# 01power.net
KiCad netlist of a schematic drawn in Altium Designer
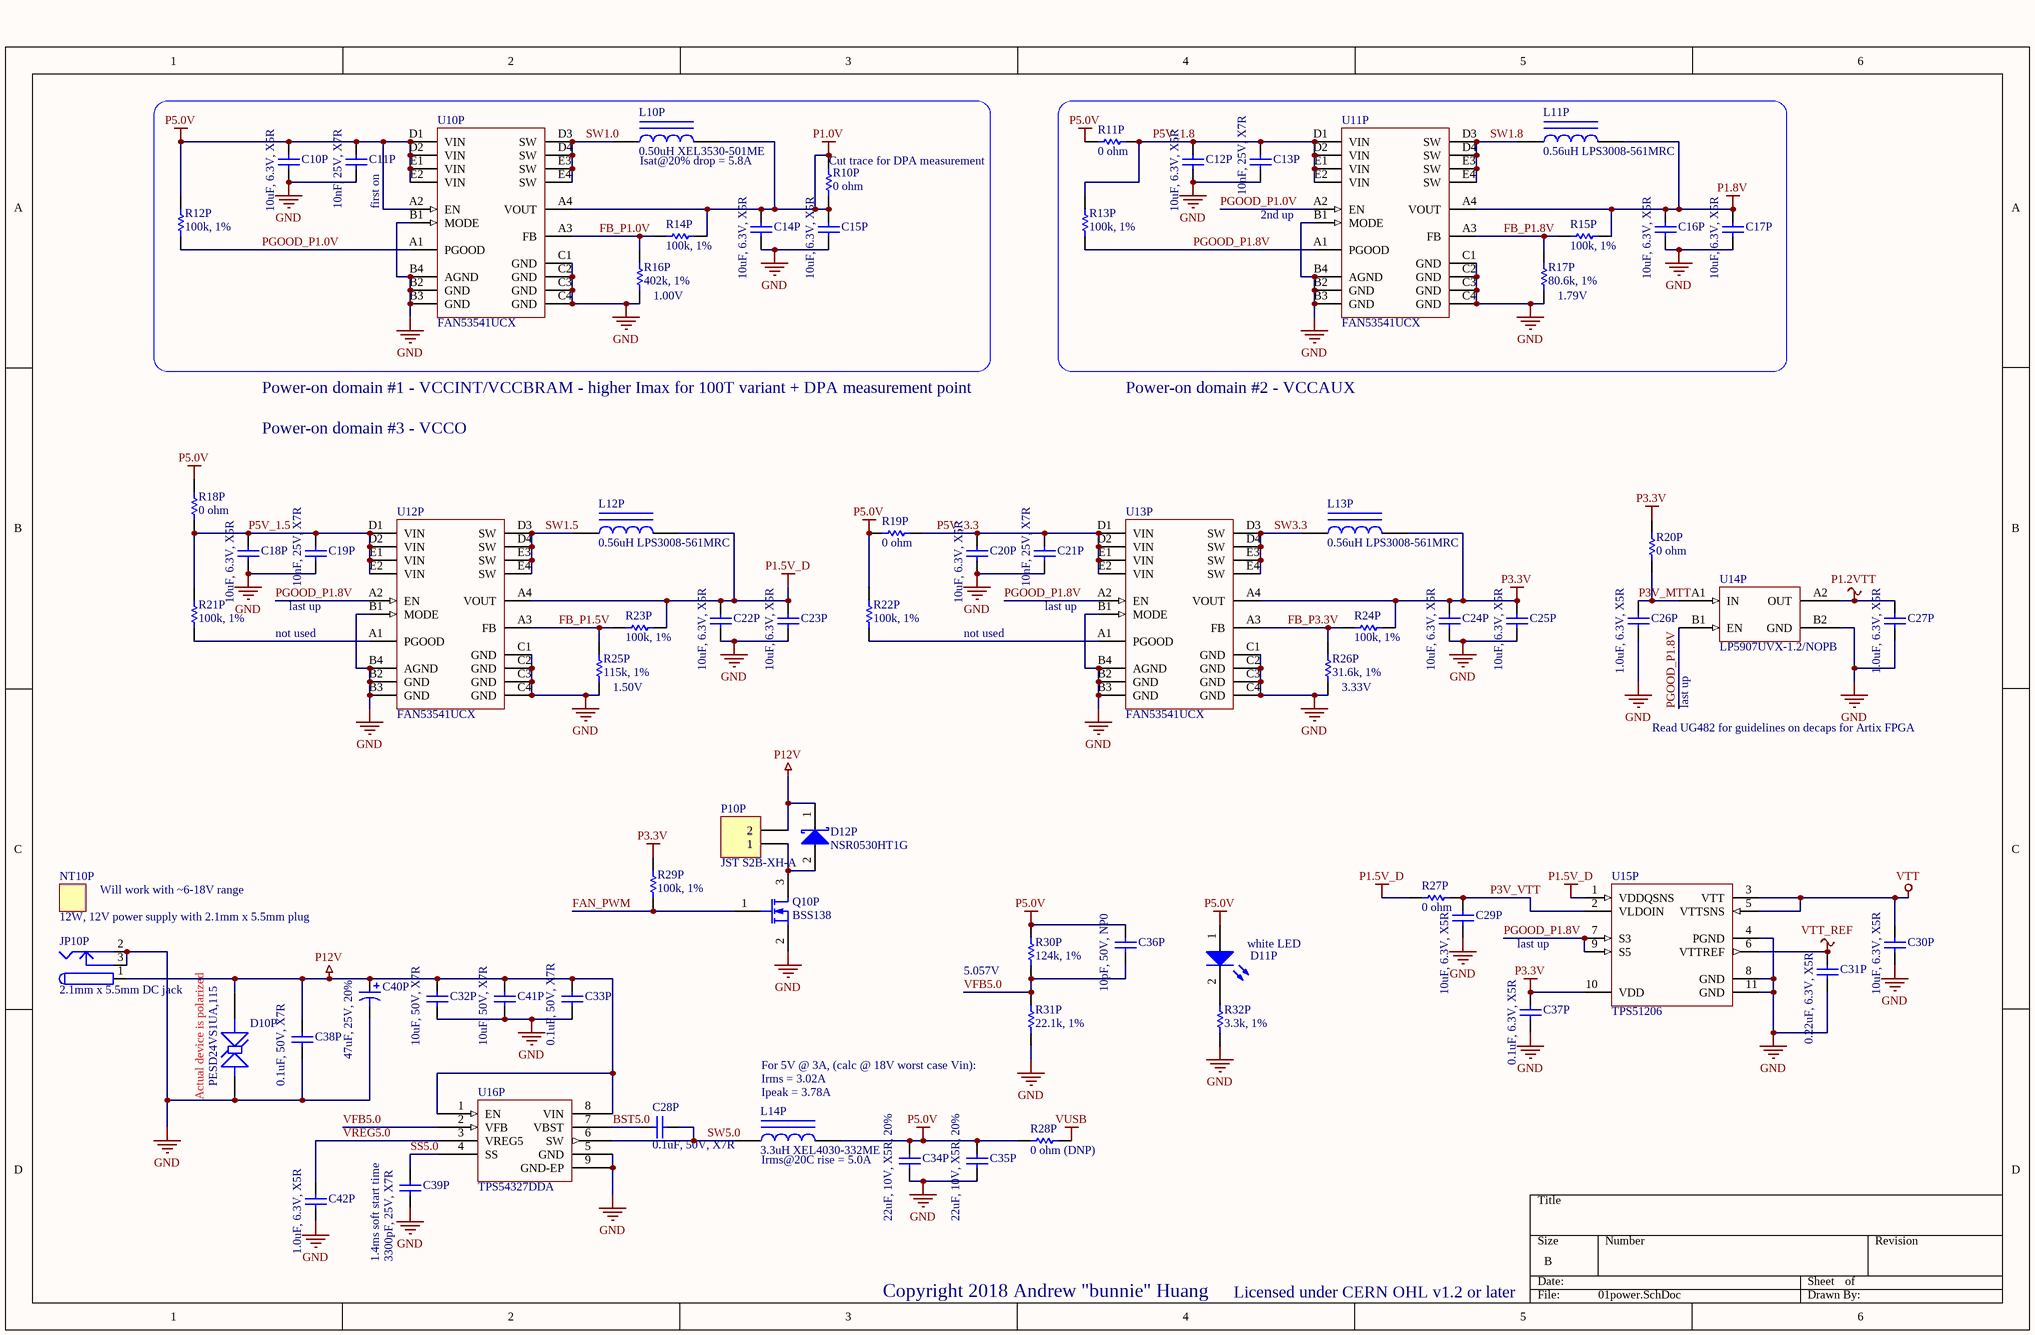
[diagram p0: 01power.SchDoc]

(export (version "E")
  (design (tool "Eeschema 10.0.6"))
  (components
    (comp (ref "C10P")
      (value "10uF, 6.3V, X5R")
      (footprint "CAPC1608N")
      (description "Capacitor (Semiconductor SIM Model)")
      (fields (field (name "MPN") "CL10A106MQ8NNNC"))
      (libsource (lib "Miscellaneous Devices") (part "Cap Semi"))
    )
    (comp (ref "C11P")
      (value "10nF, 25V, X7R")
      (footprint "CAPC1005N")
      (description "Capacitor (Semiconductor SIM Model)")
      (fields (field (name "MPN") "CL05B103KA5NNNC"))
      (libsource (lib "Miscellaneous Devices") (part "Cap Semi"))
    )
    (comp (ref "C12P")
      (value "10uF, 6.3V, X5R")
      (footprint "CAPC1608N")
      (description "Capacitor (Semiconductor SIM Model)")
      (fields (field (name "MPN") "CL10A106MQ8NNNC"))
      (libsource (lib "Miscellaneous Devices") (part "Cap Semi"))
    )
    (comp (ref "C13P")
      (value "10nF, 25V, X7R")
      (footprint "CAPC1005N")
      (description "Capacitor (Semiconductor SIM Model)")
      (fields (field (name "MPN") "CL05B103KA5NNNC"))
      (libsource (lib "Miscellaneous Devices") (part "Cap Semi"))
    )
    (comp (ref "C14P")
      (value "10uF, 6.3V, X5R")
      (footprint "CAPC1608N")
      (description "Capacitor (Semiconductor SIM Model)")
      (fields (field (name "MPN") "CL10A106MQ8NNNC"))
      (libsource (lib "Miscellaneous Devices") (part "Cap Semi"))
    )
    (comp (ref "C15P")
      (value "10uF, 6.3V, X5R")
      (footprint "CAPC1608N")
      (description "Capacitor (Semiconductor SIM Model)")
      (fields (field (name "MPN") "CL10A106MQ8NNNC"))
      (libsource (lib "Miscellaneous Devices") (part "Cap Semi"))
    )
    (comp (ref "C16P")
      (value "10uF, 6.3V, X5R")
      (footprint "CAPC1608N")
      (description "Capacitor (Semiconductor SIM Model)")
      (fields (field (name "MPN") "CL10A106MQ8NNNC"))
      (libsource (lib "Miscellaneous Devices") (part "Cap Semi"))
    )
    (comp (ref "C17P")
      (value "10uF, 6.3V, X5R")
      (footprint "CAPC1608N")
      (description "Capacitor (Semiconductor SIM Model)")
      (fields (field (name "MPN") "CL10A106MQ8NNNC"))
      (libsource (lib "Miscellaneous Devices") (part "Cap Semi"))
    )
    (comp (ref "C18P")
      (value "10uF, 6.3V, X5R")
      (footprint "CAPC1608N")
      (description "Capacitor (Semiconductor SIM Model)")
      (fields (field (name "MPN") "CL10A106MQ8NNNC"))
      (libsource (lib "Miscellaneous Devices") (part "Cap Semi"))
    )
    (comp (ref "C19P")
      (value "10nF, 25V, X7R")
      (footprint "CAPC1005N")
      (description "Capacitor (Semiconductor SIM Model)")
      (fields (field (name "MPN") "CL05B103KA5NNNC"))
      (libsource (lib "Miscellaneous Devices") (part "Cap Semi"))
    )
    (comp (ref "C20P")
      (value "10uF, 6.3V, X5R")
      (footprint "CAPC1608N")
      (description "Capacitor (Semiconductor SIM Model)")
      (fields (field (name "MPN") "CL10A106MQ8NNNC"))
      (libsource (lib "Miscellaneous Devices") (part "Cap Semi"))
    )
    (comp (ref "C21P")
      (value "10nF, 25V, X7R")
      (footprint "CAPC1005N")
      (description "Capacitor (Semiconductor SIM Model)")
      (fields (field (name "MPN") "CL05B103KA5NNNC"))
      (libsource (lib "Miscellaneous Devices") (part "Cap Semi"))
    )
    (comp (ref "C22P")
      (value "10uF, 6.3V, X5R")
      (footprint "CAPC1608N")
      (description "Capacitor (Semiconductor SIM Model)")
      (fields (field (name "MPN") "CL10A106MQ8NNNC"))
      (libsource (lib "Miscellaneous Devices") (part "Cap Semi"))
    )
    (comp (ref "C23P")
      (value "10uF, 6.3V, X5R")
      (footprint "CAPC1608N")
      (description "Capacitor (Semiconductor SIM Model)")
      (fields (field (name "MPN") "CL10A106MQ8NNNC"))
      (libsource (lib "Miscellaneous Devices") (part "Cap Semi"))
    )
    (comp (ref "C24P")
      (value "10uF, 6.3V, X5R")
      (footprint "CAPC1608N")
      (description "Capacitor (Semiconductor SIM Model)")
      (fields (field (name "MPN") "CL10A106MQ8NNNC"))
      (libsource (lib "Miscellaneous Devices") (part "Cap Semi"))
    )
    (comp (ref "C25P")
      (value "10uF, 6.3V, X5R")
      (footprint "CAPC1608N")
      (description "Capacitor (Semiconductor SIM Model)")
      (fields (field (name "MPN") "CL10A106MQ8NNNC"))
      (libsource (lib "Miscellaneous Devices") (part "Cap Semi"))
    )
    (comp (ref "C26P")
      (value "1.0uF, 6.3V, X5R")
      (footprint "CAPC0603X03L")
      (description "Capacitor (Semiconductor SIM Model)")
      (fields (field (name "MPN") "CL03A105KQ3CSNC"))
      (libsource (lib "Miscellaneous Devices") (part "Cap Semi"))
    )
    (comp (ref "C27P")
      (value "1.0uF, 6.3V, X5R")
      (footprint "CAPC0603X03L")
      (description "Capacitor (Semiconductor SIM Model)")
      (fields (field (name "MPN") "CL03A105KQ3CSNC"))
      (libsource (lib "Miscellaneous Devices") (part "Cap Semi"))
    )
    (comp (ref "C28P")
      (value "0.1uF, 50V, X7R")
      (footprint "CAPC2012N")
      (description "Capacitor (Semiconductor SIM Model)")
      (fields (field (name "MPN") "CL21B104KBCNNWC"))
      (libsource (lib "Miscellaneous Devices") (part "Cap Semi"))
    )
    (comp (ref "C29P")
      (value "10uF, 6.3V, X5R")
      (footprint "CAPC1608N")
      (description "Capacitor (Semiconductor SIM Model)")
      (fields (field (name "MPN") "CL10A106MQ8NNNC"))
      (libsource (lib "Miscellaneous Devices") (part "Cap Semi"))
    )
    (comp (ref "C30P")
      (value "10uF, 6.3V, X5R")
      (footprint "CAPC1608N")
      (description "Capacitor (Semiconductor SIM Model)")
      (fields (field (name "MPN") "CL10A106MQ8NNNC"))
      (libsource (lib "Miscellaneous Devices") (part "Cap Semi"))
    )
    (comp (ref "C31P")
      (value "0.22uF, 6.3V, X5R")
      (footprint "CAPC0603X03L")
      (description "Capacitor (Semiconductor SIM Model)")
      (fields (field (name "MPN") "CL03A224MQ3NNNC"))
      (libsource (lib "Miscellaneous Devices") (part "Cap Semi"))
    )
    (comp (ref "C32P")
      (value "10uF, 50V, X7R")
      (footprint "CAPC3216N")
      (description "Capacitor (Semiconductor SIM Model)")
      (fields (field (name "MPN") "CL31A106KBHNNNE"))
      (libsource (lib "Miscellaneous Devices") (part "Cap Semi"))
    )
    (comp (ref "C33P")
      (value "0.1uF, 50V, X7R")
      (footprint "CAPC2012N")
      (description "Capacitor (Semiconductor SIM Model)")
      (fields (field (name "MPN") "CL21B104KBCNNWC"))
      (libsource (lib "Miscellaneous Devices") (part "Cap Semi"))
    )
    (comp (ref "C34P")
      (value "22uF, 10V, X5R, 20%")
      (footprint "CAPC2012N")
      (description "Capacitor (Semiconductor SIM Model)")
      (fields
        (field (name "MFG") "Murata")
        (field (name "MPN") "GRM21BR61A226ME51L")
        (field (name "PUBLISHER") "Altium Limited")
      )
      (libsource (lib "Miscellaneous Devices") (part "Cap Semi"))
    )
    (comp (ref "C35P")
      (value "22uF, 10V, X5R, 20%")
      (footprint "CAPC2012N")
      (description "Capacitor (Semiconductor SIM Model)")
      (fields
        (field (name "MFG") "Murata")
        (field (name "MPN") "GRM21BR61A226ME51L")
        (field (name "PUBLISHER") "Altium Limited")
      )
      (libsource (lib "Miscellaneous Devices") (part "Cap Semi"))
    )
    (comp (ref "C36P")
      (value "10pF, 50V, NP0")
      (footprint "CAPC1005N")
      (description "Capacitor (Semiconductor SIM Model)")
      (fields (field (name "MPN") "GCM1555C1H100JA16D"))
      (libsource (lib "Miscellaneous Devices") (part "Cap Semi"))
    )
    (comp (ref "C37P")
      (value "0.1uF, 6.3V, X5R")
      (footprint "CAPC0603X03L")
      (description "Capacitor (Semiconductor SIM Model)")
      (fields (field (name "MPN") "CL03A104KQ3NNNC"))
      (libsource (lib "Miscellaneous Devices") (part "Cap Semi"))
    )
    (comp (ref "C38P")
      (value "0.1uF, 50V, X7R")
      (footprint "CAPC2012N")
      (description "Capacitor (Semiconductor SIM Model)")
      (fields (field (name "MPN") "CL21B104KBCNNWC"))
      (libsource (lib "Miscellaneous Devices") (part "Cap Semi"))
    )
    (comp (ref "C39P")
      (value "3300pF, 25V, X7R")
      (footprint "CAPC1005N")
      (description "Capacitor (Semiconductor SIM Model)")
      (fields (field (name "MPN") "CL05B332KA5NNNC"))
      (libsource (lib "Miscellaneous Devices") (part "Cap Semi"))
    )
    (comp (ref "C40P")
      (value "47uF, 25V, 20%")
      (footprint "CAPAE7066X61N")
      (description "Polarized Capacitor (Radial)")
      (fields (field (name "MPN") "UCL1E470MCL1GS"))
      (libsource (lib "Miscellaneous Devices") (part "Cap Pol1"))
    )
    (comp (ref "C41P")
      (value "10uF, 50V, X7R")
      (footprint "CAPC3216N")
      (description "Capacitor (Semiconductor SIM Model)")
      (fields (field (name "MPN") "CL31A106KBHNNNE"))
      (libsource (lib "Miscellaneous Devices") (part "Cap Semi"))
    )
    (comp (ref "C42P")
      (value "1.0uF, 6.3V, X5R")
      (footprint "CAPC0603X03L")
      (description "Capacitor (Semiconductor SIM Model)")
      (fields (field (name "MPN") "CL03A105KQ3CSNC"))
      (libsource (lib "Miscellaneous Devices") (part "Cap Semi"))
    )
    (comp (ref "D10P")
      (value "PESD24VS1UA,115")
      (footprint "SOD-323")
      (description "Bidirectional zener diode, Vz 17.1V nom")
      (libsource (lib "commonsch") (part "BIDIR_ESD"))
    )
    (comp (ref "D11P")
      (value "white LED")
      (footprint "CD2012-0805")
      (description "Typical RED, GREEN, YELLOW, AMBER GaAs LED")
      (fields (field (name "MPN") "CB-2012QWC-P8"))
      (libsource (lib "Miscellaneous Devices") (part "LED2"))
    )
    (comp (ref "D12P")
      (value "NSR0530HT1G")
      (footprint "SOD-323")
      (description "Schottky Diode")
      (fields (field (name "MPN") "NSR0530H-D"))
      (libsource (lib "Miscellaneous Devices") (part "D Schottky"))
    )
    (comp (ref "JP10P")
      (value "2.1mm x 5.5mm DC jack")
      (footprint "CUI_PJ_002AH_SMT")
      (description "Low Voltage Power Supply Connector")
      (fields (field (name "MPN") "DC-480-2.0A-SMT") (field (name "PUBLISHER") "Altium Limited"))
      (libsource (lib "Miscellaneous Connectors") (part "PWR2.5"))
    )
    (comp (ref "L10P")
      (value "0.50uH XEL3530-501ME")
      (footprint "COILCRAFT_XEL3530")
      (description "Magnetic-Core Inductor")
      (fields (field (name "MPN") "XEL3530-501ME_"))
      (libsource (lib "Miscellaneous Devices") (part "Inductor Iron"))
    )
    (comp (ref "L11P")
      (value "0.56uH LPS3008-561MRC")
      (footprint "COILCRAFT_LPS3008")
      (description "Magnetic-Core Inductor")
      (fields (field (name "MPN") "LPS3008-561MRC"))
      (libsource (lib "Miscellaneous Devices") (part "Inductor Iron"))
    )
    (comp (ref "L12P")
      (value "0.56uH LPS3008-561MRC")
      (footprint "COILCRAFT_LPS3008")
      (description "Magnetic-Core Inductor")
      (fields (field (name "MPN") "LPS3008-561MRC"))
      (libsource (lib "Miscellaneous Devices") (part "Inductor Iron"))
    )
    (comp (ref "L13P")
      (value "0.56uH LPS3008-561MRC")
      (footprint "COILCRAFT_LPS3008")
      (description "Magnetic-Core Inductor")
      (fields (field (name "MPN") "LPS3008-561MRC"))
      (libsource (lib "Miscellaneous Devices") (part "Inductor Iron"))
    )
    (comp (ref "L14P")
      (value "3.3uH XEL4030-332ME")
      (footprint "COILCRAFT_XEL4030")
      (description "Magnetic-Core Inductor")
      (fields (field (name "MPN") "XEL4030-332ME_"))
      (libsource (lib "Miscellaneous Devices") (part "Inductor Iron"))
    )
    (comp (ref "NT10P")
      (value "12W, 12V power supply with 2.1mm x 5.5mm plug")
      (description "Placeholder for non-board BOM items")
      (fields (field (name "MPN") "ANY"))
      (libsource (lib "commonsch") (part "NOTE"))
    )
    (comp (ref "P10P")
      (value "JST S2B-XH-A")
      (footprint "JST_S2B_XH_A")
      (description "Header, 2-Pin")
      (fields (field (name "MPN") "S2B-XH-A"))
      (libsource (lib "Miscellaneous Connectors") (part "Header 2"))
    )
    (comp (ref "Q10P")
      (value "BSS138")
      (footprint "SOT23-3N")
      (description "N-Channel MOSFET")
      (fields (field (name "MPN") "BSS138LT1G") (field (name "PUBLISHER") "Altium Limited"))
      (libsource (lib "Miscellaneous Devices") (part "MOSFET-N"))
    )
    (comp (ref "R10P")
      (value "0 ohm")
      (footprint "RESC1608N")
      (description "Resistor")
      (fields (field (name "MPN") "ANY"))
      (libsource (lib "Miscellaneous Devices") (part "Res1"))
    )
    (comp (ref "R11P")
      (value "0 ohm")
      (footprint "RESC1608N")
      (description "Resistor")
      (fields (field (name "MPN") "ANY"))
      (libsource (lib "Miscellaneous Devices") (part "Res1"))
    )
    (comp (ref "R12P")
      (value "100k, 1%")
      (footprint "RESC1005N")
      (description "Resistor")
      (fields (field (name "MPN") "ANY"))
      (libsource (lib "Miscellaneous Devices") (part "Res1"))
    )
    (comp (ref "R13P")
      (value "100k, 1%")
      (footprint "RESC1005N")
      (description "Resistor")
      (fields (field (name "MPN") "ANY"))
      (libsource (lib "Miscellaneous Devices") (part "Res1"))
    )
    (comp (ref "R14P")
      (value "100k, 1%")
      (footprint "RESC1005N")
      (description "Resistor")
      (fields (field (name "MPN") "ANY"))
      (libsource (lib "Miscellaneous Devices") (part "Res1"))
    )
    (comp (ref "R15P")
      (value "100k, 1%")
      (footprint "RESC1005N")
      (description "Resistor")
      (fields (field (name "MPN") "ANY"))
      (libsource (lib "Miscellaneous Devices") (part "Res1"))
    )
    (comp (ref "R16P")
      (value "402k, 1%")
      (footprint "RESC1005N")
      (description "Resistor")
      (fields (field (name "MPN") "ANY"))
      (libsource (lib "Miscellaneous Devices") (part "Res1"))
    )
    (comp (ref "R17P")
      (value "80.6k, 1%")
      (footprint "RESC1005N")
      (description "Resistor")
      (fields (field (name "MPN") "ANY"))
      (libsource (lib "Miscellaneous Devices") (part "Res1"))
    )
    (comp (ref "R18P")
      (value "0 ohm")
      (footprint "RESC1608N")
      (description "Resistor")
      (fields (field (name "MPN") "ANY"))
      (libsource (lib "Miscellaneous Devices") (part "Res1"))
    )
    (comp (ref "R19P")
      (value "0 ohm")
      (footprint "RESC1608N")
      (description "Resistor")
      (fields (field (name "MPN") "ANY"))
      (libsource (lib "Miscellaneous Devices") (part "Res1"))
    )
    (comp (ref "R20P")
      (value "0 ohm")
      (footprint "RESC1608N")
      (description "Resistor")
      (fields (field (name "MPN") "ANY"))
      (libsource (lib "Miscellaneous Devices") (part "Res1"))
    )
    (comp (ref "R21P")
      (value "100k, 1%")
      (footprint "RESC1005N")
      (description "Resistor")
      (fields (field (name "MPN") "ANY"))
      (libsource (lib "Miscellaneous Devices") (part "Res1"))
    )
    (comp (ref "R22P")
      (value "100k, 1%")
      (footprint "RESC1005N")
      (description "Resistor")
      (fields (field (name "MPN") "ANY"))
      (libsource (lib "Miscellaneous Devices") (part "Res1"))
    )
    (comp (ref "R23P")
      (value "100k, 1%")
      (footprint "RESC1005N")
      (description "Resistor")
      (fields (field (name "MPN") "ANY"))
      (libsource (lib "Miscellaneous Devices") (part "Res1"))
    )
    (comp (ref "R24P")
      (value "100k, 1%")
      (footprint "RESC1005N")
      (description "Resistor")
      (fields (field (name "MPN") "ANY"))
      (libsource (lib "Miscellaneous Devices") (part "Res1"))
    )
    (comp (ref "R25P")
      (value "115k, 1%")
      (footprint "RESC1005N")
      (description "Resistor")
      (fields (field (name "MPN") "ANY"))
      (libsource (lib "Miscellaneous Devices") (part "Res1"))
    )
    (comp (ref "R26P")
      (value "31.6k, 1%")
      (footprint "RESC1005N")
      (description "Resistor")
      (fields (field (name "MPN") "ANY"))
      (libsource (lib "Miscellaneous Devices") (part "Res1"))
    )
    (comp (ref "R27P")
      (value "0 ohm")
      (footprint "RESC1608N")
      (description "Resistor")
      (fields (field (name "MPN") "ANY"))
      (libsource (lib "Miscellaneous Devices") (part "Res1"))
    )
    (comp (ref "R28P")
      (value "0 ohm (DNP)")
      (footprint "RESC1608N")
      (description "Resistor")
      (fields (field (name "MPN") "DNP"))
      (libsource (lib "Miscellaneous Devices") (part "Res1"))
    )
    (comp (ref "R29P")
      (value "100k, 1%")
      (footprint "RESC1005N")
      (description "Resistor")
      (fields (field (name "MPN") "ANY"))
      (libsource (lib "Miscellaneous Devices") (part "Res1"))
    )
    (comp (ref "R30P")
      (value "124k, 1%")
      (footprint "RESC1005N")
      (description "Resistor")
      (fields (field (name "MPN") "ANY"))
      (libsource (lib "Miscellaneous Devices") (part "Res1"))
    )
    (comp (ref "R31P")
      (value "22.1k, 1%")
      (footprint "RESC1005N")
      (description "Resistor")
      (fields (field (name "MPN") "ANY"))
      (libsource (lib "Miscellaneous Devices") (part "Res1"))
    )
    (comp (ref "R32P")
      (value "3.3k, 1%")
      (footprint "RESC1005N")
      (description "Resistor")
      (fields (field (name "MPN") "RS02U332FT") (field (name "PUBLISHER") "Altium Limited"))
      (libsource (lib "Miscellaneous Devices") (part "Res1"))
    )
    (comp (ref "U10P")
      (value "FAN53541UCX")
      (footprint "BGA20C40P4X5_156X196X62")
      (description "2.4MHz, 5A TinyBuck Synchronous Buck Regulator")
      (libsource (lib "commonsch-new") (part "FAN53541UCX"))
    )
    (comp (ref "U11P")
      (value "FAN53541UCX")
      (footprint "BGA20C40P4X5_156X196X62")
      (description "2.4MHz, 5A TinyBuck Synchronous Buck Regulator")
      (libsource (lib "commonsch-new") (part "FAN53541UCX"))
    )
    (comp (ref "U12P")
      (value "FAN53541UCX")
      (footprint "BGA20C40P4X5_156X196X62")
      (description "2.4MHz, 5A TinyBuck Synchronous Buck Regulator")
      (libsource (lib "commonsch-new") (part "FAN53541UCX"))
    )
    (comp (ref "U13P")
      (value "FAN53541UCX")
      (footprint "BGA20C40P4X5_156X196X62")
      (description "2.4MHz, 5A TinyBuck Synchronous Buck Regulator")
      (libsource (lib "commonsch-new") (part "FAN53541UCX"))
    )
    (comp (ref "U14P")
      (value "LP5907UVX-1.2/NOPB")
      (footprint "TI_YKE004")
      (description "Ultra low-noise 250mA LDO for RF and analog in DSBGA")
      (libsource (lib "commonsch-new") (part "LP5907UVX"))
    )
    (comp (ref "U15P")
      (value "TPS51206")
      (footprint "TI-DSQ-R-PWSON-N10")
      (description "2A-peak sink/source DDR termination regulator")
      (fields (field (name "MPN") "TPS51206DSQ(T/R)"))
      (libsource (lib "temp-to-merge") (part "TPS51206"))
    )
    (comp (ref "U16P")
      (value "TPS54327DDA")
      (footprint "SOIC127P600-8DN")
      (description "3-A Output Single Synchronous Step-Down Buck with Integrated FET")
      (fields (field (name "MPN") "TPS54327DDA(R)"))
      (libsource (lib "commonsch-new") (part "TPS54327DDA"))
    )
  )
  (nets
    (net (code "1") (name "/BST5.0") (class "Default")
      (node (ref "C28P") (pin "2") (pinfunction "2_2") (pintype "passive"))
      (node (ref "U16P") (pin "7") (pinfunction "VBST_7") (pintype "passive"))
    )
    (net (code "2") (name "/FAN_PWM") (class "Default")
      (node (ref "Q10P") (pin "1") (pinfunction "G_1") (pintype "passive"))
      (node (ref "R29P") (pin "1") (pinfunction "1_1") (pintype "passive"))
    )
    (net (code "3") (name "/FB_P1.0V") (class "Default")
      (node (ref "R14P") (pin "1") (pinfunction "1_1") (pintype "passive"))
      (node (ref "R16P") (pin "1") (pinfunction "1_1") (pintype "passive"))
      (node (ref "U10P") (pin "A3") (pinfunction "FB_A3") (pintype "passive"))
    )
    (net (code "4") (name "/FB_P1.5V") (class "Default")
      (node (ref "R23P") (pin "1") (pinfunction "1_1") (pintype "passive"))
      (node (ref "R25P") (pin "1") (pinfunction "1_1") (pintype "passive"))
      (node (ref "U12P") (pin "A3") (pinfunction "FB_A3") (pintype "passive"))
    )
    (net (code "5") (name "/FB_P1.8V") (class "Default")
      (node (ref "R15P") (pin "1") (pinfunction "1_1") (pintype "passive"))
      (node (ref "R17P") (pin "1") (pinfunction "1_1") (pintype "passive"))
      (node (ref "U11P") (pin "A3") (pinfunction "FB_A3") (pintype "passive"))
    )
    (net (code "6") (name "/FB_P3.3V") (class "Default")
      (node (ref "R24P") (pin "1") (pinfunction "1_1") (pintype "passive"))
      (node (ref "R26P") (pin "1") (pinfunction "1_1") (pintype "passive"))
      (node (ref "U13P") (pin "A3") (pinfunction "FB_A3") (pintype "passive"))
    )
    (net (code "7") (name "/P3V_MTT") (class "Default")
      (node (ref "C26P") (pin "1") (pinfunction "1_1") (pintype "passive"))
      (node (ref "R20P") (pin "1") (pinfunction "1_1") (pintype "passive"))
      (node (ref "U14P") (pin "A1") (pinfunction "IN_A1") (pintype "input"))
    )
    (net (code "8") (name "/P3V_VTT") (class "Default")
      (node (ref "C29P") (pin "1") (pinfunction "1_1") (pintype "passive"))
      (node (ref "R27P") (pin "1") (pinfunction "1_1") (pintype "passive"))
      (node (ref "U15P") (pin "2") (pinfunction "VLDOIN_2") (pintype "power_in"))
    )
    (net (code "9") (name "/P5V_1.5") (class "Default")
      (node (ref "C18P") (pin "1") (pinfunction "1_1") (pintype "passive"))
      (node (ref "C19P") (pin "1") (pinfunction "1_1") (pintype "passive"))
      (node (ref "R18P") (pin "2") (pinfunction "2_2") (pintype "passive"))
      (node (ref "R21P") (pin "1") (pinfunction "1_1") (pintype "passive"))
      (node (ref "U12P") (pin "D1") (pinfunction "VIN_D1") (pintype "power_in"))
      (node (ref "U12P") (pin "D2") (pinfunction "VIN_D2") (pintype "power_in"))
      (node (ref "U12P") (pin "E1") (pinfunction "VIN_E1") (pintype "power_in"))
      (node (ref "U12P") (pin "E2") (pinfunction "VIN_E2") (pintype "power_in"))
    )
    (net (code "10") (name "/P5V_1.8") (class "Default")
      (node (ref "C12P") (pin "1") (pinfunction "1_1") (pintype "passive"))
      (node (ref "C13P") (pin "1") (pinfunction "1_1") (pintype "passive"))
      (node (ref "R11P") (pin "2") (pinfunction "2_2") (pintype "passive"))
      (node (ref "R13P") (pin "2") (pinfunction "2_2") (pintype "passive"))
      (node (ref "U11P") (pin "D1") (pinfunction "VIN_D1") (pintype "power_in"))
      (node (ref "U11P") (pin "D2") (pinfunction "VIN_D2") (pintype "power_in"))
      (node (ref "U11P") (pin "E1") (pinfunction "VIN_E1") (pintype "power_in"))
      (node (ref "U11P") (pin "E2") (pinfunction "VIN_E2") (pintype "power_in"))
    )
    (net (code "11") (name "/P5V_3.3") (class "Default")
      (node (ref "C20P") (pin "1") (pinfunction "1_1") (pintype "passive"))
      (node (ref "C21P") (pin "1") (pinfunction "1_1") (pintype "passive"))
      (node (ref "R19P") (pin "2") (pinfunction "2_2") (pintype "passive"))
      (node (ref "U13P") (pin "D1") (pinfunction "VIN_D1") (pintype "power_in"))
      (node (ref "U13P") (pin "D2") (pinfunction "VIN_D2") (pintype "power_in"))
      (node (ref "U13P") (pin "E1") (pinfunction "VIN_E1") (pintype "power_in"))
      (node (ref "U13P") (pin "E2") (pinfunction "VIN_E2") (pintype "power_in"))
    )
    (net (code "12") (name "/PGOOD_P1.0V") (class "Default")
      (node (ref "R12P") (pin "1") (pinfunction "1_1") (pintype "passive"))
      (node (ref "U10P") (pin "A1") (pinfunction "PGOOD_A1") (pintype "open_collector"))
      (node (ref "U11P") (pin "A2") (pinfunction "EN_A2") (pintype "input"))
    )
    (net (code "13") (name "/PGOOD_P1.8V") (class "Default")
      (node (ref "R13P") (pin "1") (pinfunction "1_1") (pintype "passive"))
      (node (ref "U11P") (pin "A1") (pinfunction "PGOOD_A1") (pintype "open_collector"))
      (node (ref "U12P") (pin "A2") (pinfunction "EN_A2") (pintype "input"))
      (node (ref "U13P") (pin "A2") (pinfunction "EN_A2") (pintype "input"))
      (node (ref "U14P") (pin "B1") (pinfunction "EN_B1") (pintype "input"))
      (node (ref "U15P") (pin "7") (pinfunction "S3_7") (pintype "input"))
      (node (ref "U15P") (pin "9") (pinfunction "S5_9") (pintype "input"))
    )
    (net (code "14") (name "/SS5.0") (class "Default")
      (node (ref "C39P") (pin "1") (pinfunction "1_1") (pintype "passive"))
      (node (ref "U16P") (pin "4") (pinfunction "SS_4") (pintype "passive"))
    )
    (net (code "15") (name "/SW1.0") (class "Default")
      (node (ref "L10P") (pin "1") (pinfunction "1_1") (pintype "passive"))
      (node (ref "U10P") (pin "D3") (pinfunction "SW_D3") (pintype "power_in"))
      (node (ref "U10P") (pin "D4") (pinfunction "SW_D4") (pintype "power_in"))
      (node (ref "U10P") (pin "E3") (pinfunction "SW_E3") (pintype "power_in"))
      (node (ref "U10P") (pin "E4") (pinfunction "SW_E4") (pintype "power_in"))
    )
    (net (code "16") (name "/SW1.5") (class "Default")
      (node (ref "L12P") (pin "1") (pinfunction "1_1") (pintype "passive"))
      (node (ref "U12P") (pin "D3") (pinfunction "SW_D3") (pintype "power_in"))
      (node (ref "U12P") (pin "D4") (pinfunction "SW_D4") (pintype "power_in"))
      (node (ref "U12P") (pin "E3") (pinfunction "SW_E3") (pintype "power_in"))
      (node (ref "U12P") (pin "E4") (pinfunction "SW_E4") (pintype "power_in"))
    )
    (net (code "17") (name "/SW1.8") (class "Default")
      (node (ref "L11P") (pin "1") (pinfunction "1_1") (pintype "passive"))
      (node (ref "U11P") (pin "D3") (pinfunction "SW_D3") (pintype "power_in"))
      (node (ref "U11P") (pin "D4") (pinfunction "SW_D4") (pintype "power_in"))
      (node (ref "U11P") (pin "E3") (pinfunction "SW_E3") (pintype "power_in"))
      (node (ref "U11P") (pin "E4") (pinfunction "SW_E4") (pintype "power_in"))
    )
    (net (code "18") (name "/SW3.3") (class "Default")
      (node (ref "L13P") (pin "1") (pinfunction "1_1") (pintype "passive"))
      (node (ref "U13P") (pin "D3") (pinfunction "SW_D3") (pintype "power_in"))
      (node (ref "U13P") (pin "D4") (pinfunction "SW_D4") (pintype "power_in"))
      (node (ref "U13P") (pin "E3") (pinfunction "SW_E3") (pintype "power_in"))
      (node (ref "U13P") (pin "E4") (pinfunction "SW_E4") (pintype "power_in"))
    )
    (net (code "19") (name "/SW5.0") (class "Default")
      (node (ref "C28P") (pin "1") (pinfunction "1_1") (pintype "passive"))
      (node (ref "L14P") (pin "1") (pinfunction "1_1") (pintype "passive"))
      (node (ref "U16P") (pin "6") (pinfunction "SW_6") (pintype "output"))
    )
    (net (code "20") (name "/VFB5.0") (class "Default")
      (node (ref "C36P") (pin "2") (pinfunction "2_2") (pintype "passive"))
      (node (ref "R30P") (pin "1") (pinfunction "1_1") (pintype "passive"))
      (node (ref "R31P") (pin "2") (pinfunction "2_2") (pintype "passive"))
      (node (ref "U16P") (pin "2") (pinfunction "VFB_2") (pintype "input"))
    )
    (net (code "21") (name "/VREG5.0") (class "Default")
      (node (ref "C42P") (pin "1") (pinfunction "1_1") (pintype "passive"))
      (node (ref "U16P") (pin "3") (pinfunction "VREG5_3") (pintype "power_in"))
    )
    (net (code "22") (name "GND") (class "Default")
      (node (ref "C10P") (pin "2") (pinfunction "2_2") (pintype "passive"))
      (node (ref "C11P") (pin "2") (pinfunction "2_2") (pintype "passive"))
      (node (ref "C12P") (pin "2") (pinfunction "2_2") (pintype "passive"))
      (node (ref "C13P") (pin "2") (pinfunction "2_2") (pintype "passive"))
      (node (ref "C14P") (pin "2") (pinfunction "2_2") (pintype "passive"))
      (node (ref "C15P") (pin "2") (pinfunction "2_2") (pintype "passive"))
      (node (ref "C16P") (pin "2") (pinfunction "2_2") (pintype "passive"))
      (node (ref "C17P") (pin "2") (pinfunction "2_2") (pintype "passive"))
      (node (ref "C18P") (pin "2") (pinfunction "2_2") (pintype "passive"))
      (node (ref "C19P") (pin "2") (pinfunction "2_2") (pintype "passive"))
      (node (ref "C20P") (pin "2") (pinfunction "2_2") (pintype "passive"))
      (node (ref "C21P") (pin "2") (pinfunction "2_2") (pintype "passive"))
      (node (ref "C22P") (pin "2") (pinfunction "2_2") (pintype "passive"))
      (node (ref "C23P") (pin "2") (pinfunction "2_2") (pintype "passive"))
      (node (ref "C24P") (pin "2") (pinfunction "2_2") (pintype "passive"))
      (node (ref "C25P") (pin "2") (pinfunction "2_2") (pintype "passive"))
      (node (ref "C26P") (pin "2") (pinfunction "2_2") (pintype "passive"))
      (node (ref "C27P") (pin "2") (pinfunction "2_2") (pintype "passive"))
      (node (ref "C29P") (pin "2") (pinfunction "2_2") (pintype "passive"))
      (node (ref "C30P") (pin "2") (pinfunction "2_2") (pintype "passive"))
      (node (ref "C31P") (pin "2") (pinfunction "2_2") (pintype "passive"))
      (node (ref "C32P") (pin "1") (pinfunction "1_1") (pintype "passive"))
      (node (ref "C33P") (pin "2") (pinfunction "2_2") (pintype "passive"))
      (node (ref "C34P") (pin "2") (pinfunction "2_2") (pintype "passive"))
      (node (ref "C35P") (pin "2") (pinfunction "2_2") (pintype "passive"))
      (node (ref "C37P") (pin "2") (pinfunction "2_2") (pintype "passive"))
      (node (ref "C38P") (pin "2") (pinfunction "2_2") (pintype "passive"))
      (node (ref "C39P") (pin "2") (pinfunction "2_2") (pintype "passive"))
      (node (ref "C40P") (pin "2") (pinfunction "2_2") (pintype "passive"))
      (node (ref "C41P") (pin "1") (pinfunction "1_1") (pintype "passive"))
      (node (ref "C42P") (pin "2") (pinfunction "2_2") (pintype "passive"))
      (node (ref "D10P") (pin "2") (pinfunction "K_2") (pintype "passive"))
      (node (ref "JP10P") (pin "2") (pintype "power_in"))
      (node (ref "JP10P") (pin "3") (pintype "power_in"))
      (node (ref "Q10P") (pin "2") (pinfunction "S_2") (pintype "passive"))
      (node (ref "R16P") (pin "2") (pinfunction "2_2") (pintype "passive"))
      (node (ref "R17P") (pin "2") (pinfunction "2_2") (pintype "passive"))
      (node (ref "R25P") (pin "2") (pinfunction "2_2") (pintype "passive"))
      (node (ref "R26P") (pin "2") (pinfunction "2_2") (pintype "passive"))
      (node (ref "R31P") (pin "1") (pinfunction "1_1") (pintype "passive"))
      (node (ref "R32P") (pin "2") (pinfunction "2_2") (pintype "passive"))
      (node (ref "U10P") (pin "B1") (pinfunction "MODE_B1") (pintype "input"))
      (node (ref "U10P") (pin "B2") (pinfunction "GND_B2") (pintype "power_in"))
      (node (ref "U10P") (pin "B3") (pinfunction "GND_B3") (pintype "power_in"))
      (node (ref "U10P") (pin "B4") (pinfunction "AGND_B4") (pintype "power_in"))
      (node (ref "U10P") (pin "C1") (pinfunction "GND_C1") (pintype "power_in"))
      (node (ref "U10P") (pin "C2") (pinfunction "GND_C2") (pintype "power_in"))
      (node (ref "U10P") (pin "C3") (pinfunction "GND_C3") (pintype "power_in"))
      (node (ref "U10P") (pin "C4") (pinfunction "GND_C4") (pintype "power_in"))
      (node (ref "U11P") (pin "B1") (pinfunction "MODE_B1") (pintype "input"))
      (node (ref "U11P") (pin "B2") (pinfunction "GND_B2") (pintype "power_in"))
      (node (ref "U11P") (pin "B3") (pinfunction "GND_B3") (pintype "power_in"))
      (node (ref "U11P") (pin "B4") (pinfunction "AGND_B4") (pintype "power_in"))
      (node (ref "U11P") (pin "C1") (pinfunction "GND_C1") (pintype "power_in"))
      (node (ref "U11P") (pin "C2") (pinfunction "GND_C2") (pintype "power_in"))
      (node (ref "U11P") (pin "C3") (pinfunction "GND_C3") (pintype "power_in"))
      (node (ref "U11P") (pin "C4") (pinfunction "GND_C4") (pintype "power_in"))
      (node (ref "U12P") (pin "B1") (pinfunction "MODE_B1") (pintype "input"))
      (node (ref "U12P") (pin "B2") (pinfunction "GND_B2") (pintype "power_in"))
      (node (ref "U12P") (pin "B3") (pinfunction "GND_B3") (pintype "power_in"))
      (node (ref "U12P") (pin "B4") (pinfunction "AGND_B4") (pintype "power_in"))
      (node (ref "U12P") (pin "C1") (pinfunction "GND_C1") (pintype "power_in"))
      (node (ref "U12P") (pin "C2") (pinfunction "GND_C2") (pintype "power_in"))
      (node (ref "U12P") (pin "C3") (pinfunction "GND_C3") (pintype "power_in"))
      (node (ref "U12P") (pin "C4") (pinfunction "GND_C4") (pintype "power_in"))
      (node (ref "U13P") (pin "B1") (pinfunction "MODE_B1") (pintype "input"))
      (node (ref "U13P") (pin "B2") (pinfunction "GND_B2") (pintype "power_in"))
      (node (ref "U13P") (pin "B3") (pinfunction "GND_B3") (pintype "power_in"))
      (node (ref "U13P") (pin "B4") (pinfunction "AGND_B4") (pintype "power_in"))
      (node (ref "U13P") (pin "C1") (pinfunction "GND_C1") (pintype "power_in"))
      (node (ref "U13P") (pin "C2") (pinfunction "GND_C2") (pintype "power_in"))
      (node (ref "U13P") (pin "C3") (pinfunction "GND_C3") (pintype "power_in"))
      (node (ref "U13P") (pin "C4") (pinfunction "GND_C4") (pintype "power_in"))
      (node (ref "U14P") (pin "B2") (pinfunction "GND_B2") (pintype "power_in"))
      (node (ref "U15P") (pin "11") (pinfunction "GND_11") (pintype "power_in"))
      (node (ref "U15P") (pin "4") (pinfunction "PGND_4") (pintype "power_in"))
      (node (ref "U15P") (pin "8") (pinfunction "GND_8") (pintype "power_in"))
      (node (ref "U16P") (pin "5") (pinfunction "GND_5") (pintype "power_in"))
      (node (ref "U16P") (pin "9") (pinfunction "GND-EP_9") (pintype "power_in"))
    )
    (net (code "23") (name "Net-(D11P-K)") (class "Default")
      (node (ref "D11P") (pin "2") (pinfunction "K_2") (pintype "passive"))
      (node (ref "R32P") (pin "1") (pinfunction "1_1") (pintype "passive"))
    )
    (net (code "24") (name "Net-(D12P-A)") (class "Default")
      (node (ref "D12P") (pin "2") (pinfunction "A_2") (pintype "passive"))
      (node (ref "P10P") (pin "1") (pinfunction "1_1") (pintype "passive"))
      (node (ref "Q10P") (pin "3") (pinfunction "D_3") (pintype "passive"))
    )
    (net (code "25") (name "Net-(U12P-PGOOD)") (class "Default")
      (node (ref "R21P") (pin "2") (pinfunction "2_2") (pintype "passive"))
      (node (ref "U12P") (pin "A1") (pinfunction "PGOOD_A1") (pintype "open_collector"))
    )
    (net (code "26") (name "Net-(U13P-PGOOD)") (class "Default")
      (node (ref "R22P") (pin "1") (pinfunction "1_1") (pintype "passive"))
      (node (ref "U13P") (pin "A1") (pinfunction "PGOOD_A1") (pintype "open_collector"))
    )
    (net (code "27") (name "P1.0V") (class "Default")
      (node (ref "C14P") (pin "1") (pinfunction "1_1") (pintype "passive"))
      (node (ref "C15P") (pin "1") (pinfunction "1_1") (pintype "passive"))
      (node (ref "L10P") (pin "2") (pinfunction "2_2") (pintype "passive"))
      (node (ref "R10P") (pin "1") (pinfunction "1_1") (pintype "passive"))
      (node (ref "R10P") (pin "2") (pinfunction "2_2") (pintype "passive"))
      (node (ref "R14P") (pin "2") (pinfunction "2_2") (pintype "passive"))
      (node (ref "U10P") (pin "A4") (pinfunction "VOUT_A4") (pintype "passive"))
    )
    (net (code "28") (name "P1.2VTT") (class "Default")
      (node (ref "C27P") (pin "1") (pinfunction "1_1") (pintype "passive"))
      (node (ref "U14P") (pin "A2") (pinfunction "OUT_A2") (pintype "power_in"))
    )
    (net (code "29") (name "P1.5V_D") (class "Default")
      (node (ref "C22P") (pin "1") (pinfunction "1_1") (pintype "passive"))
      (node (ref "C23P") (pin "1") (pinfunction "1_1") (pintype "passive"))
      (node (ref "L12P") (pin "2") (pinfunction "2_2") (pintype "passive"))
      (node (ref "R23P") (pin "2") (pinfunction "2_2") (pintype "passive"))
      (node (ref "R27P") (pin "2") (pinfunction "2_2") (pintype "passive"))
      (node (ref "U12P") (pin "A4") (pinfunction "VOUT_A4") (pintype "passive"))
      (node (ref "U15P") (pin "1") (pinfunction "VDDQSNS_1") (pintype "input"))
    )
    (net (code "30") (name "P1.8V") (class "Default")
      (node (ref "C16P") (pin "1") (pinfunction "1_1") (pintype "passive"))
      (node (ref "C17P") (pin "1") (pinfunction "1_1") (pintype "passive"))
      (node (ref "L11P") (pin "2") (pinfunction "2_2") (pintype "passive"))
      (node (ref "R15P") (pin "2") (pinfunction "2_2") (pintype "passive"))
      (node (ref "U11P") (pin "A4") (pinfunction "VOUT_A4") (pintype "passive"))
    )
    (net (code "31") (name "P3.3V") (class "Default")
      (node (ref "C24P") (pin "1") (pinfunction "1_1") (pintype "passive"))
      (node (ref "C25P") (pin "1") (pinfunction "1_1") (pintype "passive"))
      (node (ref "C37P") (pin "1") (pinfunction "1_1") (pintype "passive"))
      (node (ref "L13P") (pin "2") (pinfunction "2_2") (pintype "passive"))
      (node (ref "R20P") (pin "2") (pinfunction "2_2") (pintype "passive"))
      (node (ref "R24P") (pin "2") (pinfunction "2_2") (pintype "passive"))
      (node (ref "R29P") (pin "2") (pinfunction "2_2") (pintype "passive"))
      (node (ref "U13P") (pin "A4") (pinfunction "VOUT_A4") (pintype "passive"))
      (node (ref "U15P") (pin "10") (pinfunction "VDD_10") (pintype "power_in"))
    )
    (net (code "32") (name "P5.0V") (class "Default")
      (node (ref "C10P") (pin "1") (pinfunction "1_1") (pintype "passive"))
      (node (ref "C11P") (pin "1") (pinfunction "1_1") (pintype "passive"))
      (node (ref "C34P") (pin "1") (pinfunction "1_1") (pintype "passive"))
      (node (ref "C35P") (pin "1") (pinfunction "1_1") (pintype "passive"))
      (node (ref "C36P") (pin "1") (pinfunction "1_1") (pintype "passive"))
      (node (ref "D11P") (pin "1") (pinfunction "A_1") (pintype "passive"))
      (node (ref "L14P") (pin "2") (pinfunction "2_2") (pintype "passive"))
      (node (ref "R11P") (pin "1") (pinfunction "1_1") (pintype "passive"))
      (node (ref "R12P") (pin "2") (pinfunction "2_2") (pintype "passive"))
      (node (ref "R18P") (pin "1") (pinfunction "1_1") (pintype "passive"))
      (node (ref "R19P") (pin "1") (pinfunction "1_1") (pintype "passive"))
      (node (ref "R22P") (pin "2") (pinfunction "2_2") (pintype "passive"))
      (node (ref "R28P") (pin "1") (pinfunction "1_1") (pintype "passive"))
      (node (ref "R30P") (pin "2") (pinfunction "2_2") (pintype "passive"))
      (node (ref "U10P") (pin "A2") (pinfunction "EN_A2") (pintype "input"))
      (node (ref "U10P") (pin "D1") (pinfunction "VIN_D1") (pintype "power_in"))
      (node (ref "U10P") (pin "D2") (pinfunction "VIN_D2") (pintype "power_in"))
      (node (ref "U10P") (pin "E1") (pinfunction "VIN_E1") (pintype "power_in"))
      (node (ref "U10P") (pin "E2") (pinfunction "VIN_E2") (pintype "power_in"))
    )
    (net (code "33") (name "P12V") (class "Default")
      (node (ref "C32P") (pin "2") (pinfunction "2_2") (pintype "passive"))
      (node (ref "C33P") (pin "1") (pinfunction "1_1") (pintype "passive"))
      (node (ref "C38P") (pin "1") (pinfunction "1_1") (pintype "passive"))
      (node (ref "C40P") (pin "1") (pinfunction "1_1") (pintype "passive"))
      (node (ref "C41P") (pin "2") (pinfunction "2_2") (pintype "passive"))
      (node (ref "D10P") (pin "1") (pinfunction "A_1") (pintype "passive"))
      (node (ref "D12P") (pin "1") (pinfunction "K_1") (pintype "passive"))
      (node (ref "JP10P") (pin "1") (pintype "power_in"))
      (node (ref "P10P") (pin "2") (pinfunction "2_2") (pintype "passive"))
      (node (ref "U16P") (pin "1") (pinfunction "EN_1") (pintype "input"))
      (node (ref "U16P") (pin "8") (pinfunction "VIN_8") (pintype "power_in"))
    )
    (net (code "34") (name "VTT") (class "Default")
      (node (ref "C30P") (pin "1") (pinfunction "1_1") (pintype "passive"))
      (node (ref "U15P") (pin "3") (pinfunction "VTT_3") (pintype "power_in"))
      (node (ref "U15P") (pin "5") (pinfunction "VTTSNS_5") (pintype "input"))
    )
    (net (code "35") (name "VTT_REF") (class "Default")
      (node (ref "C31P") (pin "1") (pinfunction "1_1") (pintype "passive"))
      (node (ref "U15P") (pin "6") (pinfunction "VTTREF_6") (pintype "output"))
    )
    (net (code "36") (name "VUSB") (class "Default")
      (node (ref "R28P") (pin "2") (pinfunction "2_2") (pintype "passive"))
    )
  )
)
